# GPS.net
KiCad netlist of a schematic drawn in Altium Designer
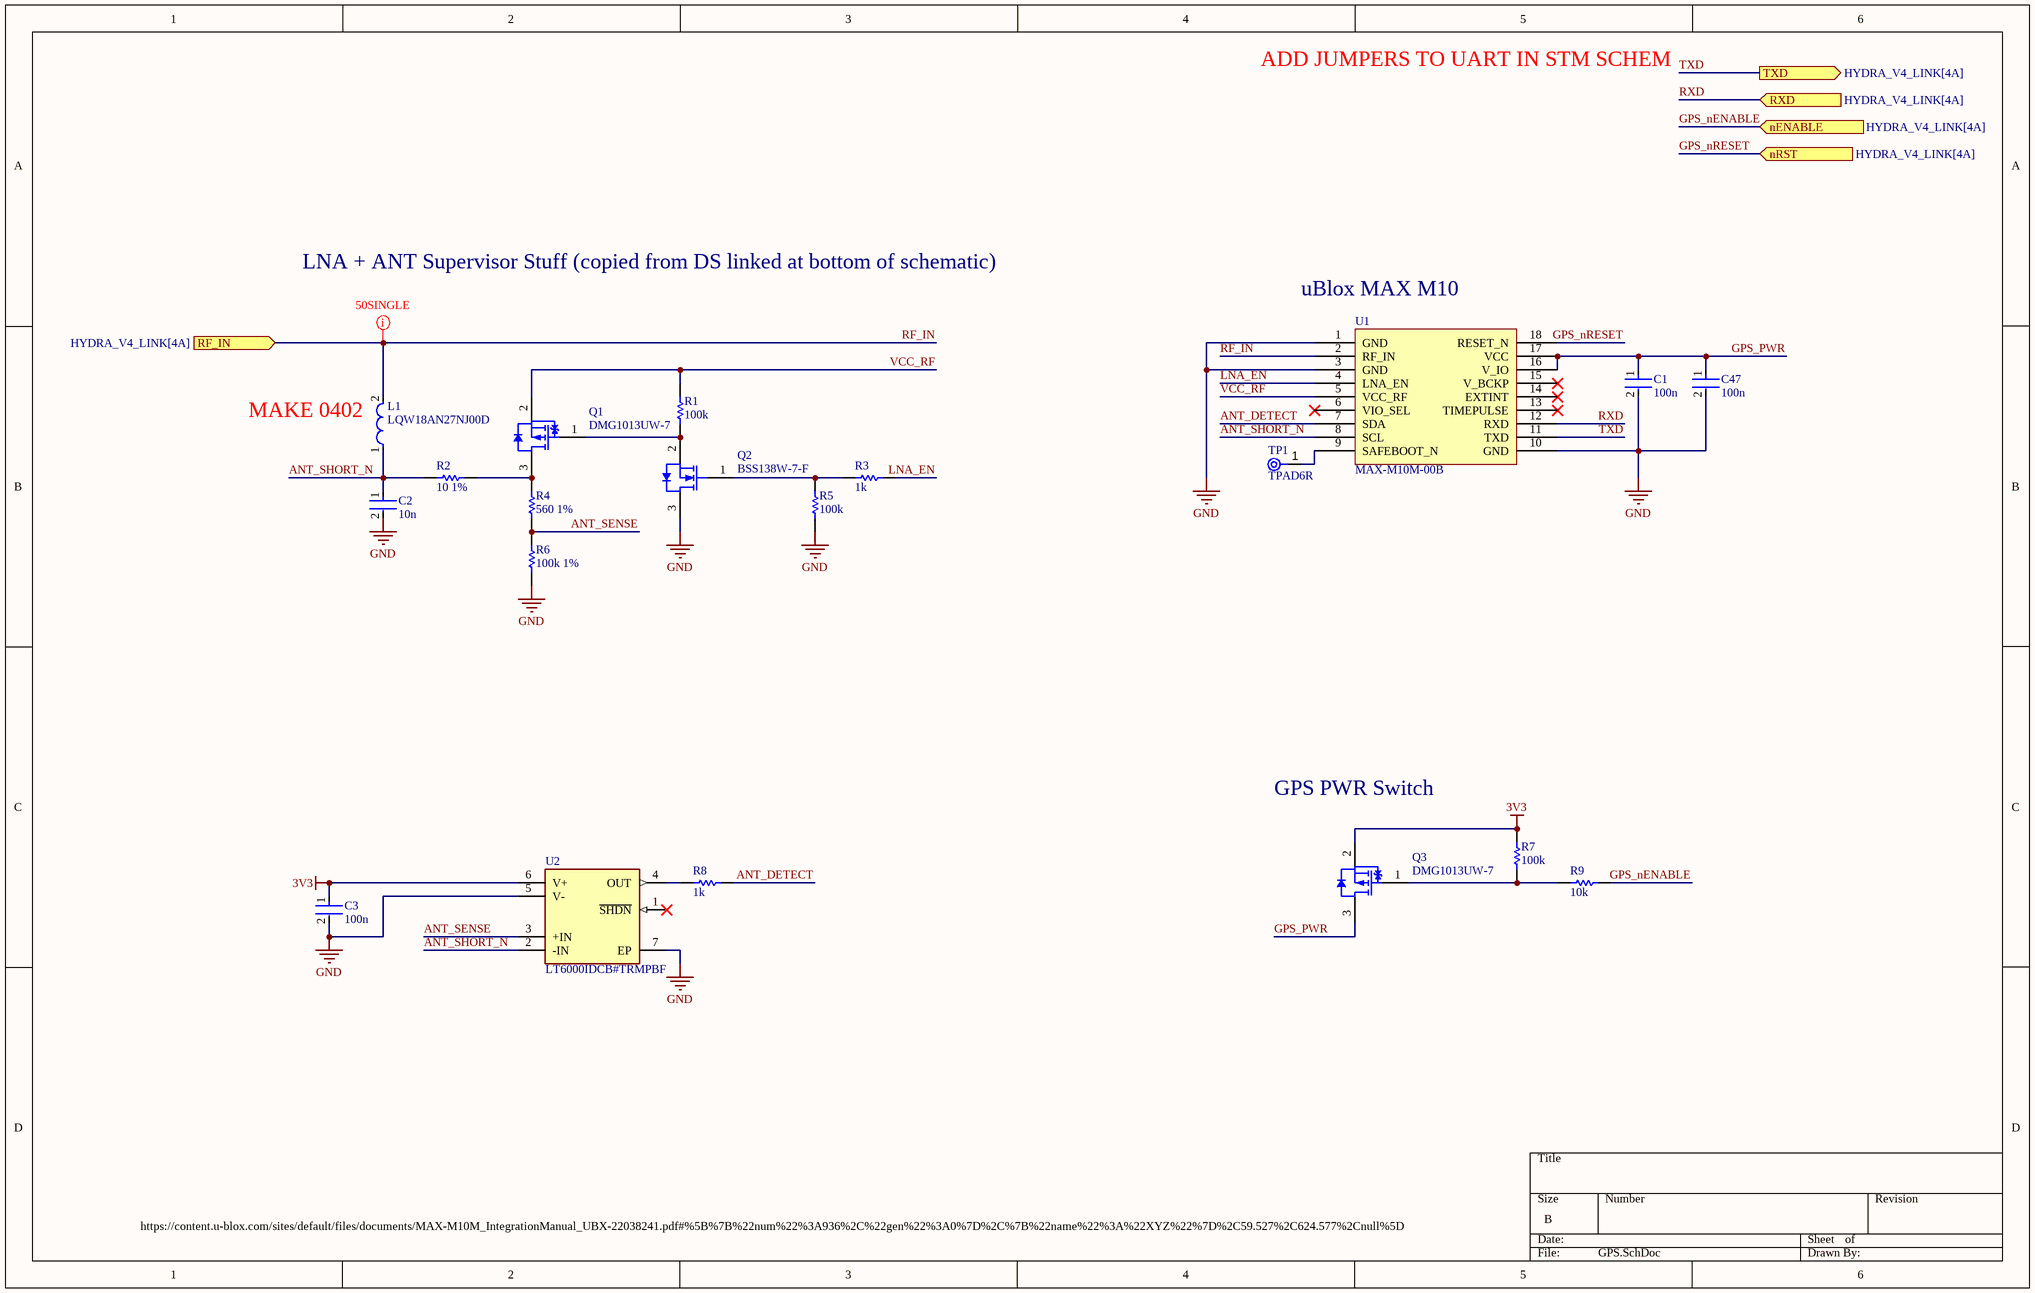
[diagram p0: GPS.SchDoc]

(export (version "E")
  (design (tool "Eeschema 10.0.6"))
  (components
    (comp (ref "C1")
      (value "100n")
      (footprint "FP-0402-L_1_0_0_05-W_0_5-IPC_A")
      (description "LARGE PADS, 0402 CAP, CHANGE COMMENT TO MATCH REAL P/N")
      (libsource (lib "Space Concordia") (part "b4654b650e69147ec39a6b967a45e02"))
    )
    (comp (ref "C2")
      (value "10n")
      (footprint "FP-0402-L_1_0_0_05-W_0_5-IPC_A")
      (description "LARGE PADS, 0402 CAP, CHANGE COMMENT TO MATCH REAL P/N")
      (libsource (lib "Space Concordia") (part "b4654b650e69147ec39a6b967a45e02"))
    )
    (comp (ref "C3")
      (value "100n")
      (footprint "FP-0402-L_1_0_0_05-W_0_5-IPC_A")
      (description "LARGE PADS, 0402 CAP, CHANGE COMMENT TO MATCH REAL P/N")
      (libsource (lib "Space Concordia") (part "b4654b650e69147ec39a6b967a45e02"))
    )
    (comp (ref "C47")
      (value "100n")
      (footprint "FP-0402-L_1_0_0_05-W_0_5-IPC_A")
      (description "LARGE PADS, 0402 CAP, CHANGE COMMENT TO MATCH REAL P/N")
      (libsource (lib "Space Concordia") (part "b4654b650e69147ec39a6b967a45e02"))
    )
    (comp (ref "L1")
      (value "LQW18AN27NJ00D")
      (footprint "FP-LQW18AN_00-MFG")
      (description "Wire Wound RF Inductor 27nH ±5% 440mA 0.21Ω 0603 (1608)")
      (fields (field (name "TOLERANCE") "5%"))
      (libsource (lib "Altium Content Vault") (part "725321dda6339637d4d059423bc1c3c"))
    )
    (comp (ref "Q1")
      (value "DMG1013UW-7")
      (footprint "DIOD-SOT323-3_V")
      (fields (field (name "MANUFACTURER") "Diodes Inc"))
      (libsource (lib "Altium Content Vault") (part "PEMOS-GSD-3_C"))
    )
    (comp (ref "Q2")
      (value "BSS138W-7-F")
      (footprint "DIOD-SOT323-3_V")
      (fields (field (name "MANUFACTURER") "DiodesIncorporated"))
      (libsource (lib "Altium Content Vault") (part "NEMOS-GSD-3"))
    )
    (comp (ref "Q3")
      (value "DMG1013UW-7")
      (footprint "DIOD-SOT323-3_V")
      (fields (field (name "MANUFACTURER") "Diodes Inc"))
      (libsource (lib "Altium Content Vault") (part "PEMOS-GSD-3_C"))
    )
    (comp (ref "R1")
      (value "100k")
      (footprint "R0603B")
      (description "Resistor")
      (libsource (lib "Space Concordia") (part "Resistor"))
    )
    (comp (ref "R2")
      (value "10 1%")
      (footprint "R0603B")
      (description "Resistor")
      (libsource (lib "Space Concordia") (part "Resistor"))
    )
    (comp (ref "R3")
      (value "1k")
      (footprint "R0603B")
      (description "Resistor")
      (libsource (lib "Space Concordia") (part "Resistor"))
    )
    (comp (ref "R4")
      (value "560 1%")
      (footprint "R0603B")
      (description "Resistor")
      (libsource (lib "Space Concordia") (part "Resistor"))
    )
    (comp (ref "R5")
      (value "100k")
      (footprint "R0603B")
      (description "Resistor")
      (libsource (lib "Space Concordia") (part "Resistor"))
    )
    (comp (ref "R6")
      (value "100k 1%")
      (footprint "R0603B")
      (description "Resistor")
      (libsource (lib "Space Concordia") (part "Resistor"))
    )
    (comp (ref "R7")
      (value "100k")
      (footprint "R0603B")
      (description "Resistor")
      (libsource (lib "Space Concordia") (part "Resistor"))
    )
    (comp (ref "R8")
      (value "1k")
      (footprint "R0603B")
      (description "Resistor")
      (libsource (lib "Space Concordia") (part "Resistor"))
    )
    (comp (ref "R9")
      (value "10k")
      (footprint "R0603B")
      (description "Resistor")
      (libsource (lib "Space Concordia") (part "Resistor"))
    )
    (comp (ref "TP1")
      (value "TPAD6R")
      (footprint "New footprint 1")
      (description "Test Point .6mm")
      (libsource (lib "Space Concordia") (part "TP"))
    )
    (comp (ref "U1")
      (value "MAX-M10M-00B")
      (footprint "MAX-M10M-00B-Footprint-1")
      (description "Gnss Lcc Rx Mod, Rom, Crystal")
      (libsource (lib "Space Concordia") (part "MAX-M10M-00B"))
    )
    (comp (ref "U2")
      (value "LT6000IDCB#TRMPBF")
      (footprint "FP-DCB-6-05-08-1715-MFG")
      (description "IC OPAMP GP 1 CIRCUIT 6DFN")
      (libsource (lib "Altium Content Vault") (part "33bb285994f2e703f79bf9d86341a8a"))
    )
  )
  (nets
    (net (code "1") (name "/ANT_DETECT") (class "Default")
      (node (ref "R8") (pin "1") (pinfunction "1_1") (pintype "passive"))
      (node (ref "U1") (pin "7") (pinfunction "SDA_7") (pintype "passive"))
    )
    (net (code "2") (name "/ANT_SENSE") (class "Default")
      (node (ref "R4") (pin "2") (pinfunction "2_2") (pintype "passive"))
      (node (ref "R6") (pin "1") (pinfunction "1_1") (pintype "passive"))
      (node (ref "U2") (pin "3") (pinfunction "+IN_3") (pintype "tri_state"))
    )
    (net (code "3") (name "/ANT_SHORT_N") (class "Default")
      (node (ref "C2") (pin "1") (pinfunction "1_1") (pintype "passive"))
      (node (ref "L1") (pin "1") (pinfunction "1_1") (pintype "passive"))
      (node (ref "R2") (pin "2") (pinfunction "2_2") (pintype "passive"))
      (node (ref "U1") (pin "8") (pinfunction "SCL_8") (pintype "passive"))
      (node (ref "U2") (pin "2") (pinfunction "-IN_2") (pintype "tri_state"))
    )
    (net (code "4") (name "/GPS_PWR") (class "Default")
      (node (ref "C1") (pin "1") (pinfunction "1_1") (pintype "passive"))
      (node (ref "C47") (pin "1") (pinfunction "1_1") (pintype "passive"))
      (node (ref "Q3") (pin "3") (pinfunction "D_3") (pintype "passive"))
      (node (ref "U1") (pin "16") (pinfunction "V_IO_16") (pintype "passive"))
      (node (ref "U1") (pin "17") (pinfunction "VCC_17") (pintype "passive"))
    )
    (net (code "5") (name "/GPS_nENABLE") (class "Default")
      (node (ref "R9") (pin "1") (pinfunction "1_1") (pintype "passive"))
    )
    (net (code "6") (name "/GPS_nRESET") (class "Default")
      (node (ref "U1") (pin "18") (pinfunction "RESET_N_18") (pintype "passive"))
    )
    (net (code "7") (name "/LNA_EN") (class "Default")
      (node (ref "R3") (pin "1") (pinfunction "1_1") (pintype "passive"))
      (node (ref "U1") (pin "4") (pinfunction "LNA_EN_4") (pintype "passive"))
    )
    (net (code "8") (name "/RF_IN") (class "Default")
      (node (ref "L1") (pin "2") (pinfunction "2_2") (pintype "passive"))
      (node (ref "U1") (pin "2") (pinfunction "RF_IN_2") (pintype "passive"))
    )
    (net (code "9") (name "/RXD") (class "Default")
      (node (ref "U1") (pin "12") (pinfunction "RXD_12") (pintype "passive"))
    )
    (net (code "10") (name "/TXD") (class "Default")
      (node (ref "U1") (pin "11") (pinfunction "TXD_11") (pintype "passive"))
    )
    (net (code "11") (name "/VCC_RF") (class "Default")
      (node (ref "Q1") (pin "2") (pinfunction "S_2") (pintype "passive"))
      (node (ref "R1") (pin "1") (pinfunction "1_1") (pintype "passive"))
      (node (ref "U1") (pin "5") (pinfunction "VCC_RF_5") (pintype "passive"))
    )
    (net (code "12") (name "3V3") (class "Default")
      (node (ref "C3") (pin "1") (pinfunction "1_1") (pintype "passive"))
      (node (ref "Q3") (pin "2") (pinfunction "S_2") (pintype "passive"))
      (node (ref "R7") (pin "2") (pinfunction "2_2") (pintype "passive"))
      (node (ref "U2") (pin "6") (pinfunction "V+_6") (pintype "power_in"))
    )
    (net (code "13") (name "GND") (class "Default")
      (node (ref "C1") (pin "2") (pinfunction "2_2") (pintype "passive"))
      (node (ref "C2") (pin "2") (pinfunction "2_2") (pintype "passive"))
      (node (ref "C3") (pin "2") (pinfunction "2_2") (pintype "passive"))
      (node (ref "C47") (pin "2") (pinfunction "2_2") (pintype "passive"))
      (node (ref "Q2") (pin "3") (pinfunction "D_3") (pintype "passive"))
      (node (ref "R5") (pin "2") (pinfunction "2_2") (pintype "passive"))
      (node (ref "R6") (pin "2") (pinfunction "2_2") (pintype "passive"))
      (node (ref "U1") (pin "1") (pinfunction "GND_1") (pintype "passive"))
      (node (ref "U1") (pin "10") (pinfunction "GND_10") (pintype "passive"))
      (node (ref "U1") (pin "3") (pinfunction "GND_3") (pintype "passive"))
      (node (ref "U2") (pin "5") (pinfunction "V-_5") (pintype "power_in"))
      (node (ref "U2") (pin "7") (pinfunction "EP_7") (pintype "power_in"))
    )
    (net (code "14") (name "Net-(Q1-D)") (class "Default")
      (node (ref "Q1") (pin "3") (pinfunction "D_3") (pintype "passive"))
      (node (ref "R2") (pin "1") (pinfunction "1_1") (pintype "passive"))
      (node (ref "R4") (pin "1") (pinfunction "1_1") (pintype "passive"))
    )
    (net (code "15") (name "Net-(Q1-G)") (class "Default")
      (node (ref "Q1") (pin "1") (pinfunction "G_1") (pintype "passive"))
      (node (ref "Q2") (pin "2") (pinfunction "S_2") (pintype "passive"))
      (node (ref "R1") (pin "2") (pinfunction "2_2") (pintype "passive"))
    )
    (net (code "16") (name "Net-(Q2-G)") (class "Default")
      (node (ref "Q2") (pin "1") (pinfunction "G_1") (pintype "passive"))
      (node (ref "R3") (pin "2") (pinfunction "2_2") (pintype "passive"))
      (node (ref "R5") (pin "1") (pinfunction "1_1") (pintype "passive"))
    )
    (net (code "17") (name "Net-(Q3-G)") (class "Default")
      (node (ref "Q3") (pin "1") (pinfunction "G_1") (pintype "passive"))
      (node (ref "R7") (pin "1") (pinfunction "1_1") (pintype "passive"))
      (node (ref "R9") (pin "2") (pinfunction "2_2") (pintype "passive"))
    )
    (net (code "18") (name "Net-(TP1-TP)") (class "Default")
      (node (ref "TP1") (pin "1") (pinfunction "TP_1") (pintype "passive"))
      (node (ref "U1") (pin "9") (pinfunction "SAFEBOOT_N_9") (pintype "passive"))
    )
    (net (code "19") (name "Net-(U2-OUT)") (class "Default")
      (node (ref "R8") (pin "2") (pinfunction "2_2") (pintype "passive"))
      (node (ref "U2") (pin "4") (pinfunction "OUT_4") (pintype "output"))
    )
    (net (code "20") (name "unconnected-(U1-EXTINT-Pad14)") (class "Default")
      (node (ref "U1") (pin "14") (pinfunction "EXTINT_14") (pintype "passive+no_connect"))
    )
    (net (code "21") (name "unconnected-(U1-TIMEPULSE-Pad13)") (class "Default")
      (node (ref "U1") (pin "13") (pinfunction "TIMEPULSE_13") (pintype "passive+no_connect"))
    )
    (net (code "22") (name "unconnected-(U1-VIO_SEL-Pad6)") (class "Default")
      (node (ref "U1") (pin "6") (pinfunction "VIO_SEL_6") (pintype "passive+no_connect"))
    )
    (net (code "23") (name "unconnected-(U1-V_BCKP-Pad15)") (class "Default")
      (node (ref "U1") (pin "15") (pinfunction "V_BCKP_15") (pintype "passive+no_connect"))
    )
    (net (code "24") (name "unconnected-(U2-~{SHDN}-Pad1)") (class "Default")
      (node (ref "U2") (pin "1") (pinfunction "~{SHDN}_1") (pintype "input+no_connect"))
    )
  )
)
